# Power.net
KiCad netlist of a schematic drawn in Altium Designer
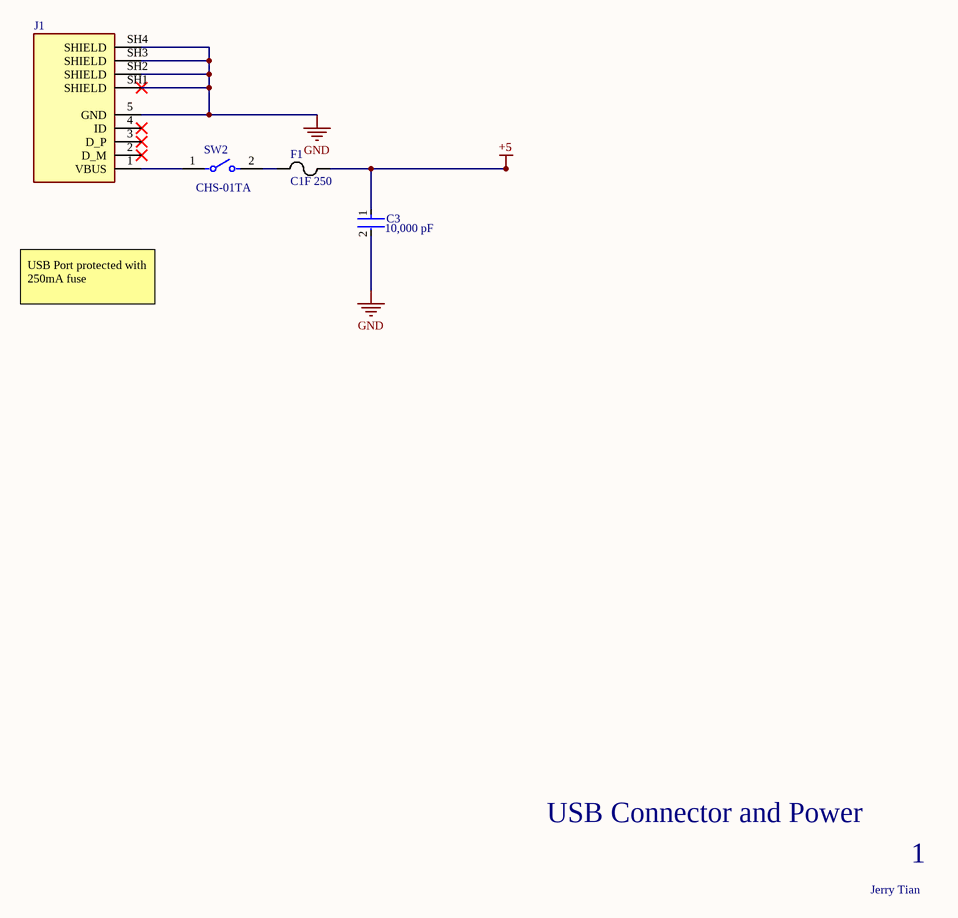
[diagram p0: Power.SchDoc]

(export (version "E")
  (design (tool "Eeschema 10.0.6"))
  (components
    (comp (ref "C3")
      (value "C1206C103K5RAC7210")
      (footprint "FP-C1206C-EB-MFG")
      (description "CAP CER 10000PF 50V X7R 1206")
      (fields
        (field (name "TOLERANCE") "0.1")
        (field (name "OCTOPART") "https://octopart.com/c1206c103k5rac7210-kemet-3918401")
        (field (name "CAPACITANCE") "10,000 pF")
      )
      (libsource (lib "Altium Content Vault") (part "b4654b650e69147ec39a6b967a45e02"))
    )
    (comp (ref "F1")
      (value "C1F 250")
      (footprint "C1_BEL")
      (description "No Description Available")
      (fields (field (name "COPYRIGHT") "Copyright (C) 2022 Ultra Librarian. All rights reserved."))
      (libsource (lib "tutorialLibrary") (part "C1F 250"))
    )
    (comp (ref "J1")
      (value "DX4R005HJ5R2000")
      (footprint "JAE_DX4R005HJ5R2000")
      (description "USB - micro B USB 2.0 Receptacle Connector 5 Position Surface Mount, Right Angle")
      (fields (field (name "MF") "JAE Electronics"))
      (libsource (lib "tutorialLibrary") (part "DX4R005HJ5R2000"))
    )
    (comp (ref "SW2")
      (value "CHS-01TA")
      (footprint "FP-CHS-01TA-MFG")
      (description "SWITCH SLIDE DIP SPST 100MA 6V")
      (fields
        (field (name "OCTOPART") "https://octopart.com/chs-01ta-nidec+copal-52304644")
        (field (name "MANUFACTURER") "Nidec Copal Electronics")
      )
      (libsource (lib "Altium Content Vault") (part "bb27bde45df87f1f469753f287ef5ae"))
    )
  )
  (nets
    (net (code "1") (name "+5") (class "Default")
      (node (ref "C3") (pin "1") (pinfunction "1_1") (pintype "passive"))
      (node (ref "F1") (pin "2") (pinfunction "2_2") (pintype "passive"))
    )
    (net (code "2") (name "GND") (class "Default")
      (node (ref "C3") (pin "2") (pinfunction "2_2") (pintype "passive"))
      (node (ref "J1") (pin "5") (pinfunction "GND_5") (pintype "passive"))
      (node (ref "J1") (pin "SH1") (pinfunction "SHIELD_SH1") (pintype "passive"))
      (node (ref "J1") (pin "SH2") (pinfunction "SHIELD_SH2") (pintype "passive"))
      (node (ref "J1") (pin "SH3") (pinfunction "SHIELD_SH3") (pintype "passive"))
      (node (ref "J1") (pin "SH4") (pinfunction "SHIELD_SH4") (pintype "passive"))
    )
    (net (code "3") (name "Net-(F1-Pad1)") (class "Default")
      (node (ref "F1") (pin "1") (pinfunction "1_1") (pintype "passive"))
      (node (ref "SW2") (pin "2") (pinfunction "2_2") (pintype "passive"))
    )
    (net (code "4") (name "Net-(J1-VBUS)") (class "Default")
      (node (ref "J1") (pin "1") (pinfunction "VBUS_1") (pintype "passive"))
      (node (ref "SW2") (pin "1") (pinfunction "1_1") (pintype "passive"))
    )
    (net (code "5") (name "unconnected-(J1-D_M-Pad2)") (class "Default")
      (node (ref "J1") (pin "2") (pinfunction "D_M_2") (pintype "passive+no_connect"))
    )
    (net (code "6") (name "unconnected-(J1-D_P-Pad3)") (class "Default")
      (node (ref "J1") (pin "3") (pinfunction "D_P_3") (pintype "passive+no_connect"))
    )
    (net (code "7") (name "unconnected-(J1-ID-Pad4)") (class "Default")
      (node (ref "J1") (pin "4") (pinfunction "ID_4") (pintype "passive+no_connect"))
    )
  )
)
